# TC_Interface.net
KiCad netlist of a schematic drawn in Altium Designer
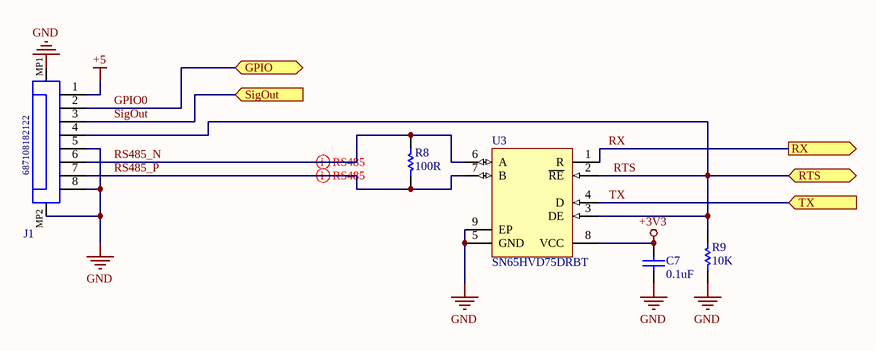
[diagram p0: TC_Interface.SchDoc]

(export (version "E")
  (design (tool "Eeschema 10.0.6"))
  (components
    (comp (ref "C7")
      (value "0.1uF")
      (footprint "CAPC1608X95X40NL15T15")
      (fields (field (name "PART NUMBER") "VJ0603Y104JXQCW1BC") (field (name "MANUFACTURER") "Vitramon"))
      (libsource (lib "Altium Content Vault") (part "CAP"))
    )
    (comp (ref "J1")
      (value "687108182122")
      (footprint "687108182122")
      (description "SMT ZIF Connectors WR-FPC, Horizontal, Back Locking Dual Contact, pitch 0.5 mm, 8 pins")
      (fields (field (name "MANUFACTURER") "Wurth Elektronik") (field (name "PUBLISHER") "WurthElektronik"))
      (libsource (lib "Altium Content Vault") (part "WE-68X1081XXX22-8"))
    )
    (comp (ref "R8")
      (value "100R")
      (footprint "RESC0603(1608)_N")
      (description "10K 0.1W 1% 0603 (1608 Metric)  SMD")
      (fields (field (name "POWER") "0.1 W") (field (name "TOLERANCE") "1 %"))
      (libsource (lib "Altium Content Vault") (part "RES"))
    )
    (comp (ref "R9")
      (value "10K")
      (footprint "RESC0603(1608)_N")
      (description "10K 0.1W 1% 0603 (1608 Metric)  SMD")
      (fields (field (name "POWER") "0.1 W") (field (name "TOLERANCE") "1 %"))
      (libsource (lib "Altium Content Vault") (part "RES"))
    )
    (comp (ref "U3")
      (value "SN65HVD75DRBT")
      (footprint "DRB0008B_V")
      (fields (field (name "MANUFACTURER") "Texas Instruments"))
      (libsource (lib "Altium Content Vault") (part "TI-SN65HVD7X-SON_DRB-8"))
    )
  )
  (nets
    (net (code "1") (name "+3V3") (class "Default")
      (node (ref "C7") (pin "2") (pinfunction "2_2") (pintype "passive"))
      (node (ref "U3") (pin "8") (pinfunction "VCC_8") (pintype "power_in"))
    )
    (net (code "2") (name "+5") (class "Default")
      (node (ref "J1") (pin "1") (pinfunction "1_1") (pintype "passive"))
    )
    (net (code "3") (name "/GPIO0") (class "Default")
      (node (ref "J1") (pin "2") (pinfunction "2_2") (pintype "passive"))
    )
    (net (code "4") (name "/RS485_N") (class "Default")
      (node (ref "J1") (pin "6") (pinfunction "6_6") (pintype "passive"))
      (node (ref "R8") (pin "1") (pinfunction "1_1") (pintype "passive"))
      (node (ref "U3") (pin "6") (pinfunction "A_6") (pintype "bidirectional"))
    )
    (net (code "5") (name "/RS485_P") (class "Default")
      (node (ref "J1") (pin "7") (pinfunction "7_7") (pintype "passive"))
      (node (ref "R8") (pin "2") (pinfunction "2_2") (pintype "passive"))
      (node (ref "U3") (pin "7") (pinfunction "B_7") (pintype "bidirectional"))
    )
    (net (code "6") (name "/RTS") (class "Default")
      (node (ref "J1") (pin "4") (pinfunction "4_4") (pintype "passive"))
      (node (ref "R9") (pin "1") (pinfunction "1_1") (pintype "passive"))
      (node (ref "U3") (pin "2") (pinfunction "~{RE}_2") (pintype "input"))
      (node (ref "U3") (pin "3") (pinfunction "DE_3") (pintype "input"))
    )
    (net (code "7") (name "/RX") (class "Default")
      (node (ref "U3") (pin "1") (pinfunction "R_1") (pintype "tri_state"))
    )
    (net (code "8") (name "/SigOut") (class "Default")
      (node (ref "J1") (pin "3") (pinfunction "3_3") (pintype "passive"))
    )
    (net (code "9") (name "/TX") (class "Default")
      (node (ref "U3") (pin "4") (pinfunction "D_4") (pintype "input"))
    )
    (net (code "10") (name "GND") (class "Default")
      (node (ref "C7") (pin "1") (pinfunction "1_1") (pintype "passive"))
      (node (ref "J1") (pin "5") (pinfunction "5_5") (pintype "passive"))
      (node (ref "J1") (pin "8") (pinfunction "8_8") (pintype "passive"))
      (node (ref "J1") (pin "MP1") (pinfunction "MP1_MP1") (pintype "passive"))
      (node (ref "J1") (pin "MP2") (pinfunction "MP2_MP2") (pintype "passive"))
      (node (ref "R9") (pin "2") (pinfunction "2_2") (pintype "passive"))
      (node (ref "U3") (pin "5") (pinfunction "GND_5") (pintype "power_in"))
      (node (ref "U3") (pin "9") (pinfunction "EP_9") (pintype "passive"))
    )
  )
)
